# 8_Inputs_Card_with_I2C_schematic.net
KiCad netlist of a schematic drawn in EasyEDA
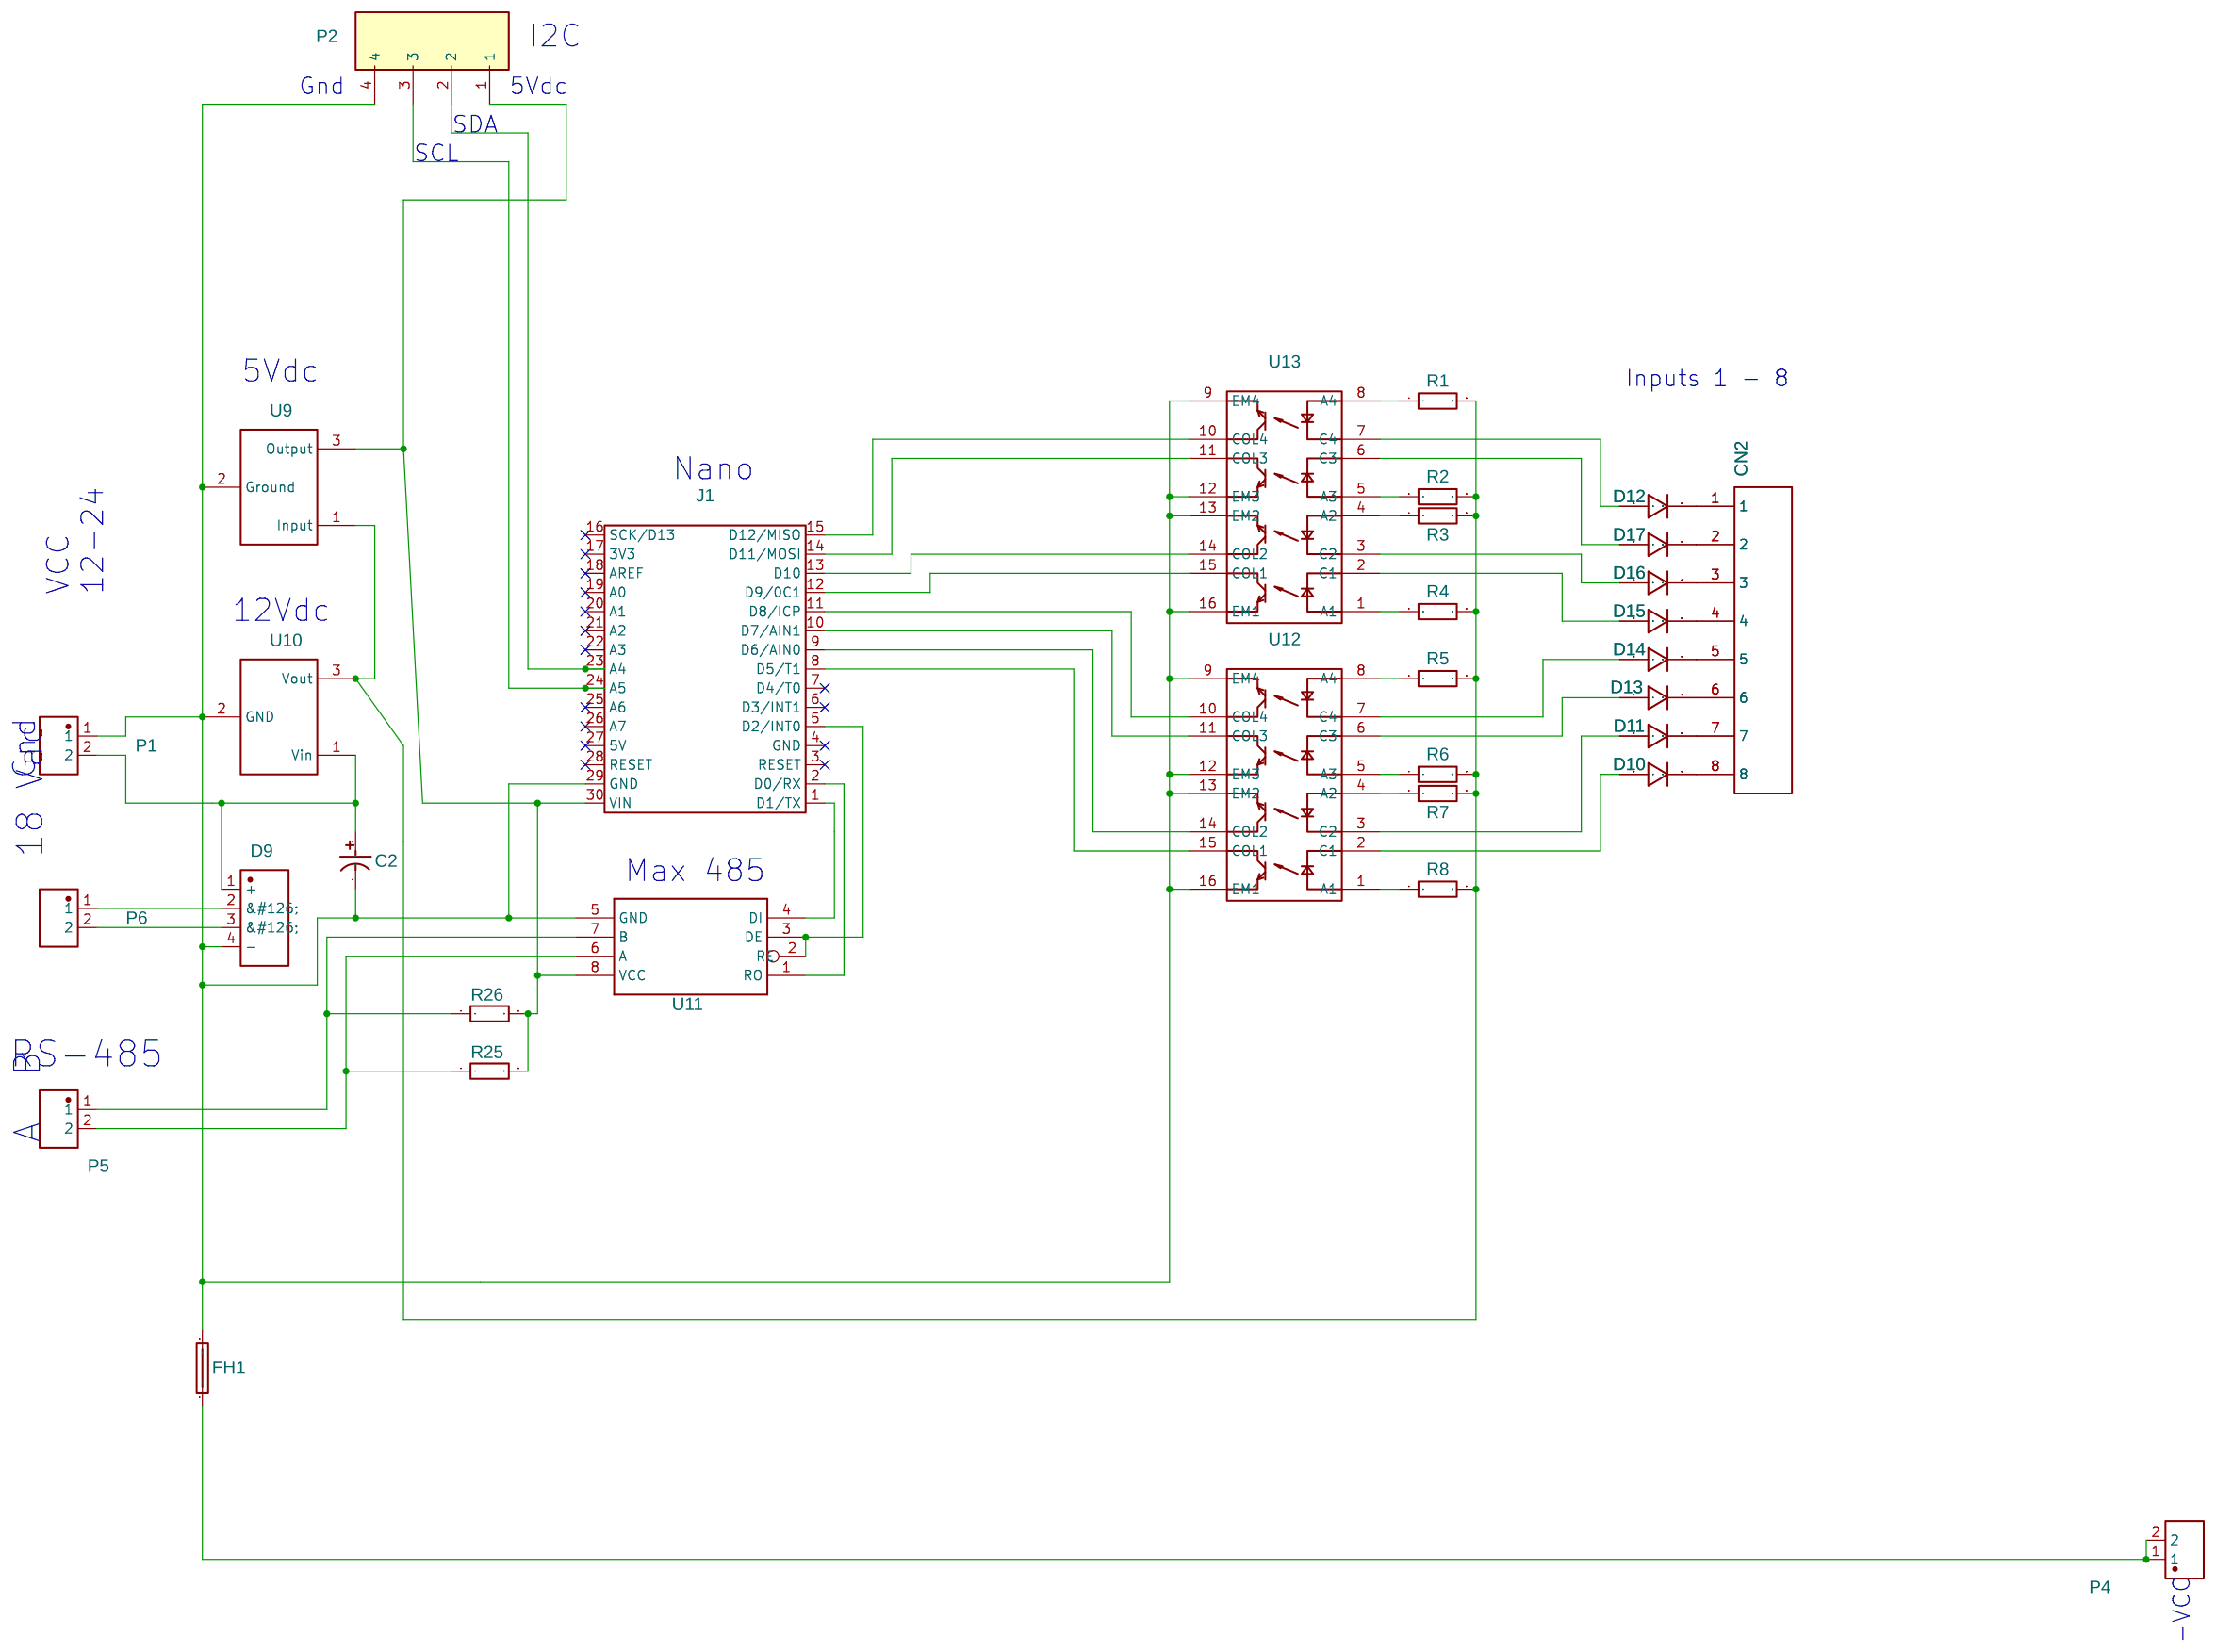
[diagram p0: schematic sheet]

(export (version "E")
  (design (tool "Eeschema 10.0.6"))
  (components
    (comp (ref "C2")
      (value "470uF")
      (fields
        (field (name "BOM_Manufacturer Part") "470uF 100V 16*25")
        (field (name "BOM_Supplier Part") "C72551")
      )
      (libsource (lib "") (part "470uF 100V 16*25"))
    )
    (comp (ref "CN2")
      (value "WJ25C-B-7.62-8P-13-00A")
      (fields (field (name "BOM_Supplier Part") "C49492"))
      (libsource (lib "") (part "Unknown_1145_360"))
    )
    (comp (ref "D9")
      (value "D50SB100")
      (fields (field (name "BOM_Supplier Part") "C411148"))
      (libsource (lib "") (part "Unknown_370_505"))
    )
    (comp (ref "D10")
      (value "1N4001")
      (fields (field (name "BOM_Supplier Part") "C169150"))
      (libsource (lib "") (part "Unknown_1105_430"))
    )
    (comp (ref "D11")
      (value "1N4001")
      (fields (field (name "BOM_Supplier Part") "C169150"))
      (libsource (lib "") (part "Unknown_1105_410"))
    )
    (comp (ref "D12")
      (value "1N4001")
      (fields (field (name "BOM_Supplier Part") "C169150"))
      (libsource (lib "") (part "Unknown_1105_290"))
    )
    (comp (ref "D13")
      (value "1N4001")
      (fields (field (name "BOM_Supplier Part") "C169150"))
      (libsource (lib "") (part "Unknown_1105_390"))
    )
    (comp (ref "D14")
      (value "1N4001")
      (fields (field (name "BOM_Supplier Part") "C169150"))
      (libsource (lib "") (part "Unknown_1105_370"))
    )
    (comp (ref "D15")
      (value "1N4001")
      (fields (field (name "BOM_Supplier Part") "C169150"))
      (libsource (lib "") (part "Unknown_1105_350"))
    )
    (comp (ref "D16")
      (value "1N4001")
      (fields (field (name "BOM_Supplier Part") "C169150"))
      (libsource (lib "") (part "Unknown_1105_330"))
    )
    (comp (ref "D17")
      (value "1N4001")
      (fields (field (name "BOM_Supplier Part") "C169150"))
      (libsource (lib "") (part "Unknown_1105_310"))
    )
    (comp (ref "FH1")
      (value "64600001003")
      (fields (field (name "BOM_Supplier Part") "C206887"))
      (libsource (lib "") (part "Unknown_345_740"))
    )
    (comp (ref "J1") (value "Arduino_Nano_Header") (libsource (lib "") (part "Unknown_605_375")))
    (comp (ref "P1")
      (value "WJ25C-B-2P")
      (fields (field (name "BOM_Supplier Part") "C8422"))
      (libsource (lib "") (part "Unknown_270_415"))
    )
    (comp (ref "P2")
      (value "WJ25C-B-4P")
      (fields (field (name "BOM_Supplier Part") "C8424"))
      (libsource (lib "") (part "WJ25C-B-4P"))
    )
    (comp (ref "P4")
      (value "WJ25C-B-2P")
      (fields (field (name "BOM_Supplier Part") "C8422"))
      (libsource (lib "") (part "Unknown_1380_835"))
    )
    (comp (ref "P5")
      (value "WJ25C-B-2P")
      (fields (field (name "BOM_Supplier Part") "C8422"))
      (libsource (lib "") (part "Unknown_270_610"))
    )
    (comp (ref "P6")
      (value "WJ25C-B-2P")
      (fields (field (name "BOM_Supplier Part") "C8422"))
      (libsource (lib "") (part "Unknown_270_505"))
    )
    (comp (ref "R1")
      (value "220")
      (fields
        (field (name "BOM_Manufacturer Part") "CFR0W4J0221A50")
        (field (name "BOM_Supplier Part") "C61289")
      )
      (libsource (lib "") (part "CFR0W4J0221A50"))
    )
    (comp (ref "R2")
      (value "220")
      (fields
        (field (name "BOM_Manufacturer Part") "CFR0W4J0221A50")
        (field (name "BOM_Supplier Part") "C61289")
      )
      (libsource (lib "") (part "CFR0W4J0221A50"))
    )
    (comp (ref "R3")
      (value "220")
      (fields
        (field (name "BOM_Manufacturer Part") "CFR0W4J0221A50")
        (field (name "BOM_Supplier Part") "C61289")
      )
      (libsource (lib "") (part "CFR0W4J0221A50"))
    )
    (comp (ref "R4")
      (value "220")
      (fields
        (field (name "BOM_Manufacturer Part") "CFR0W4J0221A50")
        (field (name "BOM_Supplier Part") "C61289")
      )
      (libsource (lib "") (part "CFR0W4J0221A50"))
    )
    (comp (ref "R5")
      (value "220")
      (fields
        (field (name "BOM_Manufacturer Part") "CFR0W4J0221A50")
        (field (name "BOM_Supplier Part") "C61289")
      )
      (libsource (lib "") (part "CFR0W4J0221A50"))
    )
    (comp (ref "R6")
      (value "220")
      (fields
        (field (name "BOM_Manufacturer Part") "CFR0W4J0221A50")
        (field (name "BOM_Supplier Part") "C61289")
      )
      (libsource (lib "") (part "CFR0W4J0221A50"))
    )
    (comp (ref "R7")
      (value "220")
      (fields
        (field (name "BOM_Manufacturer Part") "CFR0W4J0221A50")
        (field (name "BOM_Supplier Part") "C61289")
      )
      (libsource (lib "") (part "CFR0W4J0221A50"))
    )
    (comp (ref "R8")
      (value "220")
      (fields
        (field (name "BOM_Manufacturer Part") "CFR0W4J0221A50")
        (field (name "BOM_Supplier Part") "C61289")
      )
      (libsource (lib "") (part "CFR0W4J0221A50"))
    )
    (comp (ref "R25")
      (value "10K")
      (fields
        (field (name "BOM_Manufacturer Part") "CFR0W4J0103A50")
        (field (name "BOM_Supplier Part") "C61299")
      )
      (libsource (lib "") (part "CFR0W4J0103A50"))
    )
    (comp (ref "R26")
      (value "10K")
      (fields
        (field (name "BOM_Manufacturer Part") "CFR0W4J0103A50")
        (field (name "BOM_Supplier Part") "C61299")
      )
      (libsource (lib "") (part "CFR0W4J0103A50"))
    )
    (comp (ref "U9")
      (value "MC7805BTG")
      (fields (field (name "BOM_Supplier Part") "C45385"))
      (libsource (lib "") (part "Unknown_385_280"))
    )
    (comp (ref "U10")
      (value "CJ7812")
      (fields (field (name "BOM_Supplier Part") "C77894"))
      (libsource (lib "") (part "Unknown_385_400"))
    )
    (comp (ref "U11") (value "MAX485DIL") (libsource (lib "") (part "Unknown_600_520")))
    (comp (ref "U12")
      (value "ILQ2")
      (fields (field (name "BOM_Supplier Part") "C145338"))
      (libsource (lib "") (part "ILQ2"))
    )
    (comp (ref "U13")
      (value "ILQ2")
      (fields (field (name "BOM_Supplier Part") "C145338"))
      (libsource (lib "") (part "ILQ2"))
    )
  )
  (nets
    (net (code "1") (name "Net-(CN2-Pad1)") (class "Default")
      (node (ref "CN2") (pin "1") (pinfunction "1_1") (pintype "input"))
      (node (ref "D12") (pin "2") (pinfunction "2_2") (pintype "unspecified"))
    )
    (net (code "2") (name "Net-(CN2-Pad2)") (class "Default")
      (node (ref "CN2") (pin "2") (pinfunction "2_2") (pintype "input"))
      (node (ref "D17") (pin "2") (pinfunction "2_2") (pintype "unspecified"))
    )
    (net (code "3") (name "Net-(CN2-Pad3)") (class "Default")
      (node (ref "CN2") (pin "3") (pinfunction "3_3") (pintype "input"))
      (node (ref "D16") (pin "2") (pinfunction "2_2") (pintype "unspecified"))
    )
    (net (code "4") (name "Net-(CN2-Pad4)") (class "Default")
      (node (ref "CN2") (pin "4") (pinfunction "4_4") (pintype "input"))
      (node (ref "D15") (pin "2") (pinfunction "2_2") (pintype "unspecified"))
    )
    (net (code "5") (name "Net-(CN2-Pad5)") (class "Default")
      (node (ref "CN2") (pin "5") (pinfunction "5_5") (pintype "input"))
      (node (ref "D14") (pin "2") (pinfunction "2_2") (pintype "unspecified"))
    )
    (net (code "6") (name "Net-(CN2-Pad6)") (class "Default")
      (node (ref "CN2") (pin "6") (pinfunction "6_6") (pintype "input"))
      (node (ref "D13") (pin "2") (pinfunction "2_2") (pintype "unspecified"))
    )
    (net (code "7") (name "Net-(CN2-Pad7)") (class "Default")
      (node (ref "CN2") (pin "7") (pinfunction "7_7") (pintype "input"))
      (node (ref "D11") (pin "2") (pinfunction "2_2") (pintype "unspecified"))
    )
    (net (code "8") (name "Net-(CN2-Pad8)") (class "Default")
      (node (ref "CN2") (pin "8") (pinfunction "8_8") (pintype "input"))
      (node (ref "D10") (pin "2") (pinfunction "2_2") (pintype "unspecified"))
    )
    (net (code "9") (name "Net-(D9-&#126;-Pad2)") (class "Default")
      (node (ref "D9") (pin "2") (pinfunction "&#126;_2") (pintype "unspecified"))
      (node (ref "P6") (pin "1") (pinfunction "1_1") (pintype "unspecified"))
    )
    (net (code "10") (name "Net-(D9-&#126;-Pad3)") (class "Default")
      (node (ref "D9") (pin "3") (pinfunction "&#126;_3") (pintype "unspecified"))
      (node (ref "P6") (pin "2") (pinfunction "2_2") (pintype "unspecified"))
    )
    (net (code "11") (name "Net-(D9-+)") (class "Default")
      (node (ref "C2") (pin "1") (pinfunction "1_1") (pintype "input"))
      (node (ref "D9") (pin "1") (pinfunction "+_1") (pintype "unspecified"))
      (node (ref "P1") (pin "2") (pinfunction "2_2") (pintype "unspecified"))
      (node (ref "U10") (pin "1") (pinfunction "Vin_1") (pintype "unspecified"))
    )
    (net (code "12") (name "Net-(D9--)") (class "Default")
      (node (ref "C2") (pin "2") (pinfunction "2_2") (pintype "input"))
      (node (ref "D9") (pin "4") (pinfunction "-_4") (pintype "unspecified"))
      (node (ref "FH1") (pin "2") (pinfunction "2_2") (pintype "unspecified"))
      (node (ref "J1") (pin "29") (pinfunction "GND_29") (pintype "unspecified"))
      (node (ref "P1") (pin "1") (pinfunction "1_1") (pintype "unspecified"))
      (node (ref "P2") (pin "4") (pinfunction "4_4") (pintype "input"))
      (node (ref "U10") (pin "2") (pinfunction "GND_2") (pintype "unspecified"))
      (node (ref "U11") (pin "5") (pinfunction "GND_5") (pintype "unspecified"))
      (node (ref "U12") (pin "12") (pinfunction "EM3_12") (pintype "unspecified"))
      (node (ref "U12") (pin "13") (pinfunction "EM2_13") (pintype "unspecified"))
      (node (ref "U12") (pin "16") (pinfunction "EM1_16") (pintype "unspecified"))
      (node (ref "U12") (pin "9") (pinfunction "EM4_9") (pintype "unspecified"))
      (node (ref "U13") (pin "12") (pinfunction "EM3_12") (pintype "unspecified"))
      (node (ref "U13") (pin "13") (pinfunction "EM2_13") (pintype "unspecified"))
      (node (ref "U13") (pin "16") (pinfunction "EM1_16") (pintype "unspecified"))
      (node (ref "U13") (pin "9") (pinfunction "EM4_9") (pintype "unspecified"))
      (node (ref "U9") (pin "2") (pinfunction "Ground_2") (pintype "unspecified"))
    )
    (net (code "13") (name "Net-(FH1-Pad1)") (class "Default")
      (node (ref "FH1") (pin "1") (pinfunction "1_1") (pintype "unspecified"))
      (node (ref "P4") (pin "1") (pinfunction "1_1") (pintype "unspecified"))
      (node (ref "P4") (pin "2") (pinfunction "2_2") (pintype "unspecified"))
    )
    (net (code "14") (name "Net-(J1-A4)") (class "Default")
      (node (ref "J1") (pin "23") (pinfunction "A4_23") (pintype "unspecified"))
      (node (ref "P2") (pin "2") (pinfunction "2_2") (pintype "input"))
    )
    (net (code "15") (name "Net-(J1-A5)") (class "Default")
      (node (ref "J1") (pin "24") (pinfunction "A5_24") (pintype "unspecified"))
      (node (ref "P2") (pin "3") (pinfunction "3_3") (pintype "input"))
    )
    (net (code "16") (name "Net-(J1-D0{slash}RX)") (class "Default")
      (node (ref "J1") (pin "2") (pinfunction "D0/RX_2") (pintype "unspecified"))
      (node (ref "U11") (pin "1") (pinfunction "RO_1") (pintype "unspecified"))
    )
    (net (code "17") (name "Net-(J1-D1{slash}TX)") (class "Default")
      (node (ref "J1") (pin "1") (pinfunction "D1/TX_1") (pintype "unspecified"))
      (node (ref "U11") (pin "4") (pinfunction "DI_4") (pintype "unspecified"))
    )
    (net (code "18") (name "Net-(J1-D2{slash}INT0)") (class "Default")
      (node (ref "J1") (pin "5") (pinfunction "D2/INT0_5") (pintype "unspecified"))
      (node (ref "U11") (pin "2") (pinfunction "RE_2") (pintype "unspecified"))
      (node (ref "U11") (pin "3") (pinfunction "DE_3") (pintype "unspecified"))
    )
    (net (code "19") (name "Net-(J1-D5{slash}T1)") (class "Default")
      (node (ref "J1") (pin "8") (pinfunction "D5/T1_8") (pintype "unspecified"))
      (node (ref "U12") (pin "15") (pinfunction "COL1_15") (pintype "unspecified"))
    )
    (net (code "20") (name "Net-(J1-D6{slash}AIN0)") (class "Default")
      (node (ref "J1") (pin "9") (pinfunction "D6/AIN0_9") (pintype "unspecified"))
      (node (ref "U12") (pin "14") (pinfunction "COL2_14") (pintype "unspecified"))
    )
    (net (code "21") (name "Net-(J1-D7{slash}AIN1)") (class "Default")
      (node (ref "J1") (pin "10") (pinfunction "D7/AIN1_10") (pintype "unspecified"))
      (node (ref "U12") (pin "11") (pinfunction "COL3_11") (pintype "unspecified"))
    )
    (net (code "22") (name "Net-(J1-D8{slash}ICP)") (class "Default")
      (node (ref "J1") (pin "11") (pinfunction "D8/ICP_11") (pintype "unspecified"))
      (node (ref "U12") (pin "10") (pinfunction "COL4_10") (pintype "unspecified"))
    )
    (net (code "23") (name "Net-(J1-D9{slash}0C1)") (class "Default")
      (node (ref "J1") (pin "12") (pinfunction "D9/0C1_12") (pintype "unspecified"))
      (node (ref "U13") (pin "15") (pinfunction "COL1_15") (pintype "unspecified"))
    )
    (net (code "24") (name "Net-(J1-D10)") (class "Default")
      (node (ref "J1") (pin "13") (pinfunction "D10_13") (pintype "unspecified"))
      (node (ref "U13") (pin "14") (pinfunction "COL2_14") (pintype "unspecified"))
    )
    (net (code "25") (name "Net-(J1-D11{slash}MOSI)") (class "Default")
      (node (ref "J1") (pin "14") (pinfunction "D11/MOSI_14") (pintype "unspecified"))
      (node (ref "U13") (pin "11") (pinfunction "COL3_11") (pintype "unspecified"))
    )
    (net (code "26") (name "Net-(J1-D12{slash}MISO)") (class "Default")
      (node (ref "J1") (pin "15") (pinfunction "D12/MISO_15") (pintype "unspecified"))
      (node (ref "U13") (pin "10") (pinfunction "COL4_10") (pintype "unspecified"))
    )
    (net (code "27") (name "Net-(J1-VIN)") (class "Default")
      (node (ref "J1") (pin "30") (pinfunction "VIN_30") (pintype "unspecified"))
      (node (ref "P2") (pin "1") (pinfunction "1_1") (pintype "input"))
      (node (ref "R25") (pin "2") (pinfunction "2_2") (pintype "input"))
      (node (ref "R26") (pin "2") (pinfunction "2_2") (pintype "input"))
      (node (ref "U11") (pin "8") (pinfunction "VCC_8") (pintype "unspecified"))
      (node (ref "U9") (pin "3") (pinfunction "Output_3") (pintype "unspecified"))
    )
    (net (code "28") (name "Net-(U10-Vout)") (class "Default")
      (node (ref "R1") (pin "2") (pinfunction "2_2") (pintype "input"))
      (node (ref "R2") (pin "2") (pinfunction "2_2") (pintype "input"))
      (node (ref "R3") (pin "2") (pinfunction "2_2") (pintype "input"))
      (node (ref "R4") (pin "2") (pinfunction "2_2") (pintype "input"))
      (node (ref "R5") (pin "2") (pinfunction "2_2") (pintype "input"))
      (node (ref "R6") (pin "2") (pinfunction "2_2") (pintype "input"))
      (node (ref "R7") (pin "2") (pinfunction "2_2") (pintype "input"))
      (node (ref "R8") (pin "2") (pinfunction "2_2") (pintype "input"))
      (node (ref "U10") (pin "3") (pinfunction "Vout_3") (pintype "unspecified"))
      (node (ref "U9") (pin "1") (pinfunction "Input_1") (pintype "unspecified"))
    )
    (net (code "29") (name "Net-(U11-A)") (class "Default")
      (node (ref "P5") (pin "2") (pinfunction "2_2") (pintype "unspecified"))
      (node (ref "R25") (pin "1") (pinfunction "1_1") (pintype "input"))
      (node (ref "U11") (pin "6") (pinfunction "A_6") (pintype "unspecified"))
    )
    (net (code "30") (name "Net-(U11-B)") (class "Default")
      (node (ref "P5") (pin "1") (pinfunction "1_1") (pintype "unspecified"))
      (node (ref "R26") (pin "1") (pinfunction "1_1") (pintype "input"))
      (node (ref "U11") (pin "7") (pinfunction "B_7") (pintype "unspecified"))
    )
    (net (code "31") (name "Net-(U12-A1)") (class "Default")
      (node (ref "R8") (pin "1") (pinfunction "1_1") (pintype "input"))
      (node (ref "U12") (pin "1") (pinfunction "A1_1") (pintype "unspecified"))
    )
    (net (code "32") (name "Net-(U12-A2)") (class "Default")
      (node (ref "R7") (pin "1") (pinfunction "1_1") (pintype "input"))
      (node (ref "U12") (pin "4") (pinfunction "A2_4") (pintype "unspecified"))
    )
    (net (code "33") (name "Net-(U12-A3)") (class "Default")
      (node (ref "R6") (pin "1") (pinfunction "1_1") (pintype "input"))
      (node (ref "U12") (pin "5") (pinfunction "A3_5") (pintype "unspecified"))
    )
    (net (code "34") (name "Net-(U12-A4)") (class "Default")
      (node (ref "R5") (pin "1") (pinfunction "1_1") (pintype "input"))
      (node (ref "U12") (pin "8") (pinfunction "A4_8") (pintype "unspecified"))
    )
    (net (code "35") (name "Net-(U12-C1)") (class "Default")
      (node (ref "D10") (pin "1") (pinfunction "1_1") (pintype "unspecified"))
      (node (ref "U12") (pin "2") (pinfunction "C1_2") (pintype "unspecified"))
    )
    (net (code "36") (name "Net-(U12-C2)") (class "Default")
      (node (ref "D11") (pin "1") (pinfunction "1_1") (pintype "unspecified"))
      (node (ref "U12") (pin "3") (pinfunction "C2_3") (pintype "unspecified"))
    )
    (net (code "37") (name "Net-(U12-C3)") (class "Default")
      (node (ref "D13") (pin "1") (pinfunction "1_1") (pintype "unspecified"))
      (node (ref "U12") (pin "6") (pinfunction "C3_6") (pintype "unspecified"))
    )
    (net (code "38") (name "Net-(U12-C4)") (class "Default")
      (node (ref "D14") (pin "1") (pinfunction "1_1") (pintype "unspecified"))
      (node (ref "U12") (pin "7") (pinfunction "C4_7") (pintype "unspecified"))
    )
    (net (code "39") (name "Net-(U13-A1)") (class "Default")
      (node (ref "R4") (pin "1") (pinfunction "1_1") (pintype "input"))
      (node (ref "U13") (pin "1") (pinfunction "A1_1") (pintype "unspecified"))
    )
    (net (code "40") (name "Net-(U13-A2)") (class "Default")
      (node (ref "R3") (pin "1") (pinfunction "1_1") (pintype "input"))
      (node (ref "U13") (pin "4") (pinfunction "A2_4") (pintype "unspecified"))
    )
    (net (code "41") (name "Net-(U13-A3)") (class "Default")
      (node (ref "R2") (pin "1") (pinfunction "1_1") (pintype "input"))
      (node (ref "U13") (pin "5") (pinfunction "A3_5") (pintype "unspecified"))
    )
    (net (code "42") (name "Net-(U13-A4)") (class "Default")
      (node (ref "R1") (pin "1") (pinfunction "1_1") (pintype "input"))
      (node (ref "U13") (pin "8") (pinfunction "A4_8") (pintype "unspecified"))
    )
    (net (code "43") (name "Net-(U13-C1)") (class "Default")
      (node (ref "D15") (pin "1") (pinfunction "1_1") (pintype "unspecified"))
      (node (ref "U13") (pin "2") (pinfunction "C1_2") (pintype "unspecified"))
    )
    (net (code "44") (name "Net-(U13-C2)") (class "Default")
      (node (ref "D16") (pin "1") (pinfunction "1_1") (pintype "unspecified"))
      (node (ref "U13") (pin "3") (pinfunction "C2_3") (pintype "unspecified"))
    )
    (net (code "45") (name "Net-(U13-C3)") (class "Default")
      (node (ref "D17") (pin "1") (pinfunction "1_1") (pintype "unspecified"))
      (node (ref "U13") (pin "6") (pinfunction "C3_6") (pintype "unspecified"))
    )
    (net (code "46") (name "Net-(U13-C4)") (class "Default")
      (node (ref "D12") (pin "1") (pinfunction "1_1") (pintype "unspecified"))
      (node (ref "U13") (pin "7") (pinfunction "C4_7") (pintype "unspecified"))
    )
    (net (code "47") (name "unconnected-(J1-3V3-Pad17)") (class "Default")
      (node (ref "J1") (pin "17") (pinfunction "3V3_17") (pintype "unspecified+no_connect"))
    )
    (net (code "48") (name "unconnected-(J1-5V-Pad27)") (class "Default")
      (node (ref "J1") (pin "27") (pinfunction "5V_27") (pintype "unspecified+no_connect"))
    )
    (net (code "49") (name "unconnected-(J1-A0-Pad19)") (class "Default")
      (node (ref "J1") (pin "19") (pinfunction "A0_19") (pintype "unspecified+no_connect"))
    )
    (net (code "50") (name "unconnected-(J1-A1-Pad20)") (class "Default")
      (node (ref "J1") (pin "20") (pinfunction "A1_20") (pintype "unspecified+no_connect"))
    )
    (net (code "51") (name "unconnected-(J1-A2-Pad21)") (class "Default")
      (node (ref "J1") (pin "21") (pinfunction "A2_21") (pintype "unspecified+no_connect"))
    )
    (net (code "52") (name "unconnected-(J1-A3-Pad22)") (class "Default")
      (node (ref "J1") (pin "22") (pinfunction "A3_22") (pintype "unspecified+no_connect"))
    )
    (net (code "53") (name "unconnected-(J1-A6-Pad25)") (class "Default")
      (node (ref "J1") (pin "25") (pinfunction "A6_25") (pintype "unspecified+no_connect"))
    )
    (net (code "54") (name "unconnected-(J1-A7-Pad26)") (class "Default")
      (node (ref "J1") (pin "26") (pinfunction "A7_26") (pintype "unspecified+no_connect"))
    )
    (net (code "55") (name "unconnected-(J1-AREF-Pad18)") (class "Default")
      (node (ref "J1") (pin "18") (pinfunction "AREF_18") (pintype "unspecified+no_connect"))
    )
    (net (code "56") (name "unconnected-(J1-D3{slash}INT1-Pad6)") (class "Default")
      (node (ref "J1") (pin "6") (pinfunction "D3/INT1_6") (pintype "unspecified+no_connect"))
    )
    (net (code "57") (name "unconnected-(J1-D4{slash}T0-Pad7)") (class "Default")
      (node (ref "J1") (pin "7") (pinfunction "D4/T0_7") (pintype "unspecified+no_connect"))
    )
    (net (code "58") (name "unconnected-(J1-GND-Pad4)") (class "Default")
      (node (ref "J1") (pin "4") (pinfunction "GND_4") (pintype "unspecified+no_connect"))
    )
    (net (code "59") (name "unconnected-(J1-RESET-Pad3)") (class "Default")
      (node (ref "J1") (pin "3") (pinfunction "RESET_3") (pintype "unspecified+no_connect"))
    )
    (net (code "60") (name "unconnected-(J1-RESET-Pad28)") (class "Default")
      (node (ref "J1") (pin "28") (pinfunction "RESET_28") (pintype "unspecified+no_connect"))
    )
    (net (code "61") (name "unconnected-(J1-SCK{slash}D13-Pad16)") (class "Default")
      (node (ref "J1") (pin "16") (pinfunction "SCK/D13_16") (pintype "unspecified+no_connect"))
    )
  )
)
